# MRCS-SMC-08-Arduino-Relay.net
KiCad netlist of a schematic drawn in EAGLE
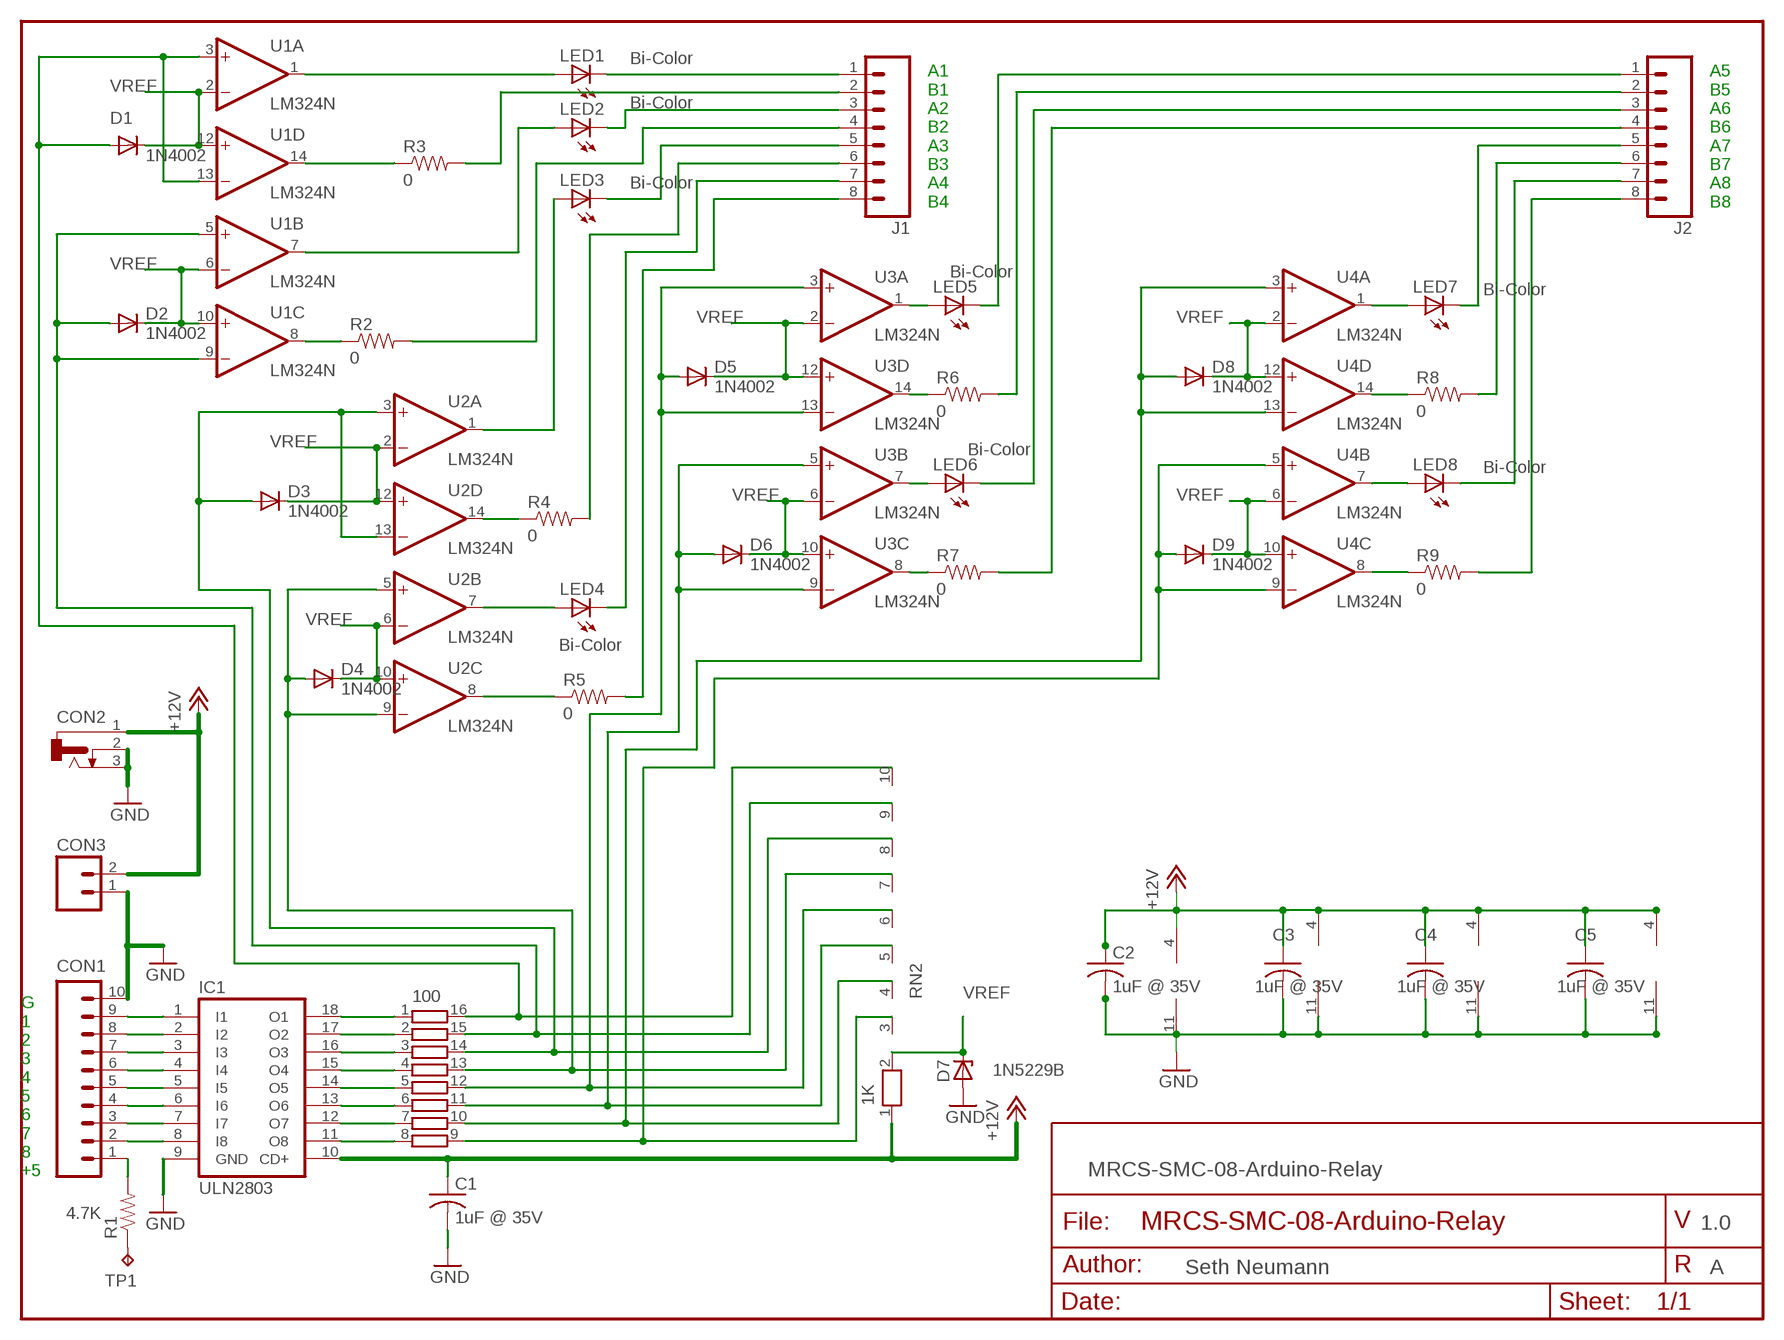
[diagram p0: schematic, sheet 1]

(export (version "E")
  (design (tool "Eeschema 10.0.6"))
  (components
    (comp (ref "C1")
      (value "1uF @ 35V")
      (footprint "eagle-import:C-PTH-0.100")
      (libsource (lib "eagle-import") (part "CAPPTH2"))
    )
    (comp (ref "C2")
      (value "1uF @ 35V")
      (footprint "eagle-import:C-PTH-0.100")
      (libsource (lib "eagle-import") (part "CAPPTH2"))
    )
    (comp (ref "C3")
      (value "1uF @ 35V")
      (footprint "eagle-import:C-PTH-0.100")
      (libsource (lib "eagle-import") (part "CAPPTH2"))
    )
    (comp (ref "C4")
      (value "1uF @ 35V")
      (footprint "eagle-import:C-PTH-0.100")
      (libsource (lib "eagle-import") (part "CAPPTH2"))
    )
    (comp (ref "C5")
      (value "1uF @ 35V")
      (footprint "eagle-import:C-PTH-0.100")
      (libsource (lib "eagle-import") (part "CAPPTH2"))
    )
    (comp (ref "CON1")
      (value "CONNECTOR-M10LOCK")
      (footprint "eagle-import:1X10_LOCK")
      (libsource (lib "eagle-import") (part "CONNECTOR-M10LOCK"))
    )
    (comp (ref "CON2")
      (value "CONNECTOR-DC-POWER-S")
      (footprint "eagle-import:DCJ0202-SMALL")
      (libsource (lib "eagle-import") (part "CONNECTOR-DC-POWER-S"))
    )
    (comp (ref "CON3")
      (value "CONNECTOR-M023.5MM-LOCK")
      (footprint "eagle-import:SCREWTERMINAL-3.5MM-2_LOCK")
      (libsource (lib "eagle-import") (part "CONNECTOR-M023.5MM-LOCK"))
    )
    (comp (ref "D1")
      (value "1N4002")
      (footprint "eagle-import:DIODE-1N4001")
      (libsource (lib "eagle-import") (part "DIODEPTH"))
    )
    (comp (ref "D2")
      (value "1N4002")
      (footprint "eagle-import:DIODE-1N4001")
      (libsource (lib "eagle-import") (part "DIODEPTH"))
    )
    (comp (ref "D3")
      (value "1N4002")
      (footprint "eagle-import:DIODE-1N4001")
      (libsource (lib "eagle-import") (part "DIODEPTH"))
    )
    (comp (ref "D4")
      (value "1N4002")
      (footprint "eagle-import:DIODE-1N4001")
      (libsource (lib "eagle-import") (part "DIODEPTH"))
    )
    (comp (ref "D5")
      (value "1N4002")
      (footprint "eagle-import:DIODE-1N4001")
      (libsource (lib "eagle-import") (part "DIODEPTH"))
    )
    (comp (ref "D6")
      (value "1N4002")
      (footprint "eagle-import:DIODE-1N4001")
      (libsource (lib "eagle-import") (part "DIODEPTH"))
    )
    (comp (ref "D7")
      (value "1N5229B")
      (footprint "eagle-import:ZDIO-5")
      (libsource (lib "eagle-import") (part "ZENER-DIODEZD-5"))
    )
    (comp (ref "D8")
      (value "1N4002")
      (footprint "eagle-import:DIODE-1N4001")
      (libsource (lib "eagle-import") (part "DIODEPTH"))
    )
    (comp (ref "D9")
      (value "1N4002")
      (footprint "eagle-import:DIODE-1N4001")
      (libsource (lib "eagle-import") (part "DIODEPTH"))
    )
    (comp (ref "IC1")
      (value "ULN2803")
      (footprint "eagle-import:DIL18")
      (libsource (lib "eagle-import") (part "ULN2803A"))
    )
    (comp (ref "J1")
      (value "CONNECTOR-M08LOCK")
      (footprint "eagle-import:1X08_LOCK")
      (libsource (lib "eagle-import") (part "CONNECTOR-M08LOCK"))
    )
    (comp (ref "J2")
      (value "CONNECTOR-M08LOCK")
      (footprint "eagle-import:1X08_LOCK")
      (libsource (lib "eagle-import") (part "CONNECTOR-M08LOCK"))
    )
    (comp (ref "LED1")
      (value "Bi-Color")
      (footprint "eagle-import:LED3MM")
      (libsource (lib "eagle-import") (part "LEDLED3MM"))
    )
    (comp (ref "LED2")
      (value "Bi-Color")
      (footprint "eagle-import:LED3MM")
      (libsource (lib "eagle-import") (part "LEDLED3MM"))
    )
    (comp (ref "LED3")
      (value "Bi-Color")
      (footprint "eagle-import:LED3MM")
      (libsource (lib "eagle-import") (part "LEDLED3MM"))
    )
    (comp (ref "LED4")
      (value "Bi-Color")
      (footprint "eagle-import:LED3MM")
      (libsource (lib "eagle-import") (part "LEDLED3MM"))
    )
    (comp (ref "LED5")
      (value "Bi-Color")
      (footprint "eagle-import:LED3MM")
      (libsource (lib "eagle-import") (part "LEDLED3MM"))
    )
    (comp (ref "LED6")
      (value "Bi-Color")
      (footprint "eagle-import:LED3MM")
      (libsource (lib "eagle-import") (part "LEDLED3MM"))
    )
    (comp (ref "LED7")
      (value "Bi-Color")
      (footprint "eagle-import:LED3MM")
      (libsource (lib "eagle-import") (part "LEDLED3MM"))
    )
    (comp (ref "LED8")
      (value "Bi-Color")
      (footprint "eagle-import:LED3MM")
      (libsource (lib "eagle-import") (part "LEDLED3MM"))
    )
    (comp (ref "R1")
      (value "4.7K")
      (footprint "eagle-import:AXIAL-0.4-RES")
      (libsource (lib "eagle-import") (part "RPTH04"))
    )
    (comp (ref "R2")
      (value "0")
      (footprint "eagle-import:CUT-R")
      (libsource (lib "eagle-import") (part "RPTH-R0"))
    )
    (comp (ref "R3")
      (value "0")
      (footprint "eagle-import:CUT-R")
      (libsource (lib "eagle-import") (part "RPTH-R0"))
    )
    (comp (ref "R4")
      (value "0")
      (footprint "eagle-import:CUT-R")
      (libsource (lib "eagle-import") (part "RPTH-R0"))
    )
    (comp (ref "R5")
      (value "0")
      (footprint "eagle-import:CUT-R")
      (libsource (lib "eagle-import") (part "RPTH-R0"))
    )
    (comp (ref "R6")
      (value "0")
      (footprint "eagle-import:CUT-R")
      (libsource (lib "eagle-import") (part "RPTH-R0"))
    )
    (comp (ref "R7")
      (value "0")
      (footprint "eagle-import:CUT-R")
      (libsource (lib "eagle-import") (part "RPTH-R0"))
    )
    (comp (ref "R8")
      (value "0")
      (footprint "eagle-import:CUT-R")
      (libsource (lib "eagle-import") (part "RPTH-R0"))
    )
    (comp (ref "R9")
      (value "0")
      (footprint "eagle-import:CUT-R")
      (libsource (lib "eagle-import") (part "RPTH-R0"))
    )
    (comp (ref "RN1")
      (value "100")
      (footprint "eagle-import:DIL16")
      (libsource (lib "eagle-import") (part "8R-N"))
    )
    (comp (ref "RN2")
      (value "1K")
      (footprint "eagle-import:RN-10")
      (libsource (lib "eagle-import") (part "RN09"))
    )
    (comp (ref "TP1")
      (value "TPPAD1-13")
      (footprint "eagle-import:P1-13")
      (libsource (lib "eagle-import") (part "TPPAD1-13"))
    )
    (comp (ref "U1")
      (value "LM324N")
      (footprint "eagle-import:DIL14")
      (libsource (lib "eagle-import") (part "LM324N"))
    )
    (comp (ref "U2")
      (value "LM324N")
      (footprint "eagle-import:DIL14")
      (libsource (lib "eagle-import") (part "LM324N"))
    )
    (comp (ref "U3")
      (value "LM324N")
      (footprint "eagle-import:DIL14")
      (libsource (lib "eagle-import") (part "LM324N"))
    )
    (comp (ref "U4")
      (value "LM324N")
      (footprint "eagle-import:DIL14")
      (libsource (lib "eagle-import") (part "LM324N"))
    )
  )
  (nets
    (net (code "1") (name "+12V") (class "Default")
      (node (ref "C1") (pin "1") (pinfunction "1_1") (pintype "passive"))
      (node (ref "C2") (pin "1") (pinfunction "1_1") (pintype "passive"))
      (node (ref "C3") (pin "1") (pinfunction "1_1") (pintype "passive"))
      (node (ref "C4") (pin "1") (pinfunction "1_1") (pintype "passive"))
      (node (ref "C5") (pin "1") (pinfunction "1_1") (pintype "passive"))
      (node (ref "CON2") (pin "1") (pinfunction "1_1") (pintype "passive"))
      (node (ref "CON3") (pin "2") (pinfunction "B_2") (pintype "passive"))
      (node (ref "IC1") (pin "10") (pinfunction "CD+_10") (pintype "passive"))
      (node (ref "RN2") (pin "1") (pinfunction "1_1") (pintype "passive"))
      (node (ref "U1") (pin "4") (pinfunction "V+_4") (pintype "power_in"))
      (node (ref "U2") (pin "4") (pinfunction "V+_4") (pintype "power_in"))
      (node (ref "U3") (pin "4") (pinfunction "V+_4") (pintype "power_in"))
      (node (ref "U4") (pin "4") (pinfunction "V+_4") (pintype "power_in"))
    )
    (net (code "2") (name "/VREF") (class "Default")
      (node (ref "D1") (pin "C") (pinfunction "C_C") (pintype "passive"))
      (node (ref "D2") (pin "C") (pinfunction "C_C") (pintype "passive"))
      (node (ref "D3") (pin "C") (pinfunction "C_C") (pintype "passive"))
      (node (ref "D4") (pin "C") (pinfunction "C_C") (pintype "passive"))
      (node (ref "D5") (pin "C") (pinfunction "C_C") (pintype "passive"))
      (node (ref "D6") (pin "C") (pinfunction "C_C") (pintype "passive"))
      (node (ref "D7") (pin "C") (pinfunction "C_C") (pintype "passive"))
      (node (ref "D8") (pin "C") (pinfunction "C_C") (pintype "passive"))
      (node (ref "D9") (pin "C") (pinfunction "C_C") (pintype "passive"))
      (node (ref "RN2") (pin "2") (pinfunction "2_2") (pintype "passive"))
      (node (ref "U1") (pin "10") (pinfunction "+IN_10") (pintype "input"))
      (node (ref "U1") (pin "12") (pinfunction "+IN_12") (pintype "input"))
      (node (ref "U1") (pin "2") (pinfunction "-IN_2") (pintype "input"))
      (node (ref "U1") (pin "6") (pinfunction "-IN_6") (pintype "input"))
      (node (ref "U2") (pin "10") (pinfunction "+IN_10") (pintype "input"))
      (node (ref "U2") (pin "12") (pinfunction "+IN_12") (pintype "input"))
      (node (ref "U2") (pin "2") (pinfunction "-IN_2") (pintype "input"))
      (node (ref "U2") (pin "6") (pinfunction "-IN_6") (pintype "input"))
      (node (ref "U3") (pin "10") (pinfunction "+IN_10") (pintype "input"))
      (node (ref "U3") (pin "12") (pinfunction "+IN_12") (pintype "input"))
      (node (ref "U3") (pin "2") (pinfunction "-IN_2") (pintype "input"))
      (node (ref "U3") (pin "6") (pinfunction "-IN_6") (pintype "input"))
      (node (ref "U4") (pin "10") (pinfunction "+IN_10") (pintype "input"))
      (node (ref "U4") (pin "12") (pinfunction "+IN_12") (pintype "input"))
      (node (ref "U4") (pin "2") (pinfunction "-IN_2") (pintype "input"))
      (node (ref "U4") (pin "6") (pinfunction "-IN_6") (pintype "input"))
    )
    (net (code "3") (name "GND") (class "Default")
      (node (ref "C1") (pin "2") (pinfunction "2_2") (pintype "passive"))
      (node (ref "C2") (pin "2") (pinfunction "2_2") (pintype "passive"))
      (node (ref "C3") (pin "2") (pinfunction "2_2") (pintype "passive"))
      (node (ref "C4") (pin "2") (pinfunction "2_2") (pintype "passive"))
      (node (ref "C5") (pin "2") (pinfunction "2_2") (pintype "passive"))
      (node (ref "CON1") (pin "10") (pinfunction "10_10") (pintype "passive"))
      (node (ref "CON2") (pin "2") (pinfunction "2_2") (pintype "passive"))
      (node (ref "CON2") (pin "3") (pinfunction "3_3") (pintype "passive"))
      (node (ref "CON3") (pin "1") (pinfunction "A_1") (pintype "passive"))
      (node (ref "D7") (pin "A") (pinfunction "A_A") (pintype "passive"))
      (node (ref "IC1") (pin "9") (pinfunction "GND_9") (pintype "power_in"))
      (node (ref "U1") (pin "11") (pinfunction "V-_11") (pintype "power_in"))
      (node (ref "U2") (pin "11") (pinfunction "V-_11") (pintype "power_in"))
      (node (ref "U3") (pin "11") (pinfunction "V-_11") (pintype "power_in"))
      (node (ref "U4") (pin "11") (pinfunction "V-_11") (pintype "power_in"))
    )
    (net (code "4") (name "Net-(IC1-I1)") (class "Default")
      (node (ref "CON1") (pin "9") (pinfunction "9_9") (pintype "passive"))
      (node (ref "IC1") (pin "1") (pinfunction "I1_1") (pintype "input"))
    )
    (net (code "5") (name "Net-(IC1-I2)") (class "Default")
      (node (ref "CON1") (pin "8") (pinfunction "8_8") (pintype "passive"))
      (node (ref "IC1") (pin "2") (pinfunction "I2_2") (pintype "input"))
    )
    (net (code "6") (name "Net-(IC1-I3)") (class "Default")
      (node (ref "CON1") (pin "7") (pinfunction "7_7") (pintype "passive"))
      (node (ref "IC1") (pin "3") (pinfunction "I3_3") (pintype "input"))
    )
    (net (code "7") (name "Net-(IC1-I4)") (class "Default")
      (node (ref "CON1") (pin "6") (pinfunction "6_6") (pintype "passive"))
      (node (ref "IC1") (pin "4") (pinfunction "I4_4") (pintype "input"))
    )
    (net (code "8") (name "Net-(IC1-I5)") (class "Default")
      (node (ref "CON1") (pin "5") (pinfunction "5_5") (pintype "passive"))
      (node (ref "IC1") (pin "5") (pinfunction "I5_5") (pintype "input"))
    )
    (net (code "9") (name "Net-(IC1-I6)") (class "Default")
      (node (ref "CON1") (pin "4") (pinfunction "4_4") (pintype "passive"))
      (node (ref "IC1") (pin "6") (pinfunction "I6_6") (pintype "input"))
    )
    (net (code "10") (name "Net-(IC1-I7)") (class "Default")
      (node (ref "CON1") (pin "3") (pinfunction "3_3") (pintype "passive"))
      (node (ref "IC1") (pin "7") (pinfunction "I7_7") (pintype "input"))
    )
    (net (code "11") (name "Net-(IC1-I8)") (class "Default")
      (node (ref "CON1") (pin "2") (pinfunction "2_2") (pintype "passive"))
      (node (ref "IC1") (pin "8") (pinfunction "I8_8") (pintype "input"))
    )
    (net (code "12") (name "Net-(IC1-O1)") (class "Default")
      (node (ref "IC1") (pin "18") (pinfunction "O1_18") (pintype "open_collector"))
      (node (ref "RN1") (pin "1") (pinfunction "1_1") (pintype "passive"))
    )
    (net (code "13") (name "Net-(IC1-O2)") (class "Default")
      (node (ref "IC1") (pin "17") (pinfunction "O2_17") (pintype "open_collector"))
      (node (ref "RN1") (pin "2") (pinfunction "1_2") (pintype "passive"))
    )
    (net (code "14") (name "Net-(IC1-O3)") (class "Default")
      (node (ref "IC1") (pin "16") (pinfunction "O3_16") (pintype "open_collector"))
      (node (ref "RN1") (pin "3") (pinfunction "1_3") (pintype "passive"))
    )
    (net (code "15") (name "Net-(IC1-O4)") (class "Default")
      (node (ref "IC1") (pin "15") (pinfunction "O4_15") (pintype "open_collector"))
      (node (ref "RN1") (pin "4") (pinfunction "1_4") (pintype "passive"))
    )
    (net (code "16") (name "Net-(IC1-O5)") (class "Default")
      (node (ref "IC1") (pin "14") (pinfunction "O5_14") (pintype "open_collector"))
      (node (ref "RN1") (pin "5") (pinfunction "1_5") (pintype "passive"))
    )
    (net (code "17") (name "Net-(IC1-O6)") (class "Default")
      (node (ref "IC1") (pin "13") (pinfunction "O6_13") (pintype "open_collector"))
      (node (ref "RN1") (pin "6") (pinfunction "1_6") (pintype "passive"))
    )
    (net (code "18") (name "Net-(IC1-O7)") (class "Default")
      (node (ref "IC1") (pin "12") (pinfunction "O7_12") (pintype "open_collector"))
      (node (ref "RN1") (pin "7") (pinfunction "1_7") (pintype "passive"))
    )
    (net (code "19") (name "Net-(IC1-O8)") (class "Default")
      (node (ref "IC1") (pin "11") (pinfunction "O8_11") (pintype "open_collector"))
      (node (ref "RN1") (pin "8") (pinfunction "1_8") (pintype "passive"))
    )
    (net (code "20") (name "Net-(LED1-C)") (class "Default")
      (node (ref "J1") (pin "1") (pinfunction "1_1") (pintype "passive"))
      (node (ref "LED1") (pin "K") (pinfunction "C_K") (pintype "passive"))
    )
    (net (code "21") (name "Net-(LED2-C)") (class "Default")
      (node (ref "J1") (pin "3") (pinfunction "3_3") (pintype "passive"))
      (node (ref "LED2") (pin "K") (pinfunction "C_K") (pintype "passive"))
    )
    (net (code "22") (name "Net-(LED3-C)") (class "Default")
      (node (ref "J1") (pin "5") (pinfunction "5_5") (pintype "passive"))
      (node (ref "LED3") (pin "K") (pinfunction "C_K") (pintype "passive"))
    )
    (net (code "23") (name "Net-(LED4-C)") (class "Default")
      (node (ref "J1") (pin "7") (pinfunction "7_7") (pintype "passive"))
      (node (ref "LED4") (pin "K") (pinfunction "C_K") (pintype "passive"))
    )
    (net (code "24") (name "Net-(LED5-C)") (class "Default")
      (node (ref "J2") (pin "1") (pinfunction "1_1") (pintype "passive"))
      (node (ref "LED5") (pin "K") (pinfunction "C_K") (pintype "passive"))
    )
    (net (code "25") (name "Net-(LED6-C)") (class "Default")
      (node (ref "J2") (pin "3") (pinfunction "3_3") (pintype "passive"))
      (node (ref "LED6") (pin "K") (pinfunction "C_K") (pintype "passive"))
    )
    (net (code "26") (name "Net-(LED7-C)") (class "Default")
      (node (ref "J2") (pin "5") (pinfunction "5_5") (pintype "passive"))
      (node (ref "LED7") (pin "K") (pinfunction "C_K") (pintype "passive"))
    )
    (net (code "27") (name "Net-(LED8-C)") (class "Default")
      (node (ref "J2") (pin "7") (pinfunction "7_7") (pintype "passive"))
      (node (ref "LED8") (pin "K") (pinfunction "C_K") (pintype "passive"))
    )
    (net (code "28") (name "Net-(R1-1)") (class "Default")
      (node (ref "R1") (pin "P$1") (pinfunction "1_P$1") (pintype "passive"))
      (node (ref "TP1") (pin "TP") (pinfunction "TP_TP") (pintype "input"))
    )
    (net (code "29") (name "Net-(R1-2)") (class "Default")
      (node (ref "CON1") (pin "1") (pinfunction "1_1") (pintype "passive"))
      (node (ref "R1") (pin "P$2") (pinfunction "2_P$2") (pintype "passive"))
    )
    (net (code "30") (name "Net-(R2-1)") (class "Default")
      (node (ref "R2") (pin "P2") (pinfunction "1_P2") (pintype "passive"))
      (node (ref "U1") (pin "8") (pinfunction "OUT_8") (pintype "output"))
    )
    (net (code "31") (name "Net-(R2-2)") (class "Default")
      (node (ref "J1") (pin "4") (pinfunction "4_4") (pintype "passive"))
      (node (ref "R2") (pin "P1") (pinfunction "2_P1") (pintype "passive"))
    )
    (net (code "32") (name "Net-(R3-1)") (class "Default")
      (node (ref "R3") (pin "P2") (pinfunction "1_P2") (pintype "passive"))
      (node (ref "U1") (pin "14") (pinfunction "OUT_14") (pintype "output"))
    )
    (net (code "33") (name "Net-(R3-2)") (class "Default")
      (node (ref "J1") (pin "2") (pinfunction "2_2") (pintype "passive"))
      (node (ref "R3") (pin "P1") (pinfunction "2_P1") (pintype "passive"))
    )
    (net (code "34") (name "Net-(R4-1)") (class "Default")
      (node (ref "R4") (pin "P2") (pinfunction "1_P2") (pintype "passive"))
      (node (ref "U2") (pin "14") (pinfunction "OUT_14") (pintype "output"))
    )
    (net (code "35") (name "Net-(R4-2)") (class "Default")
      (node (ref "J1") (pin "6") (pinfunction "6_6") (pintype "passive"))
      (node (ref "R4") (pin "P1") (pinfunction "2_P1") (pintype "passive"))
    )
    (net (code "36") (name "Net-(R5-1)") (class "Default")
      (node (ref "R5") (pin "P2") (pinfunction "1_P2") (pintype "passive"))
      (node (ref "U2") (pin "8") (pinfunction "OUT_8") (pintype "output"))
    )
    (net (code "37") (name "Net-(R5-2)") (class "Default")
      (node (ref "J1") (pin "8") (pinfunction "8_8") (pintype "passive"))
      (node (ref "R5") (pin "P1") (pinfunction "2_P1") (pintype "passive"))
    )
    (net (code "38") (name "Net-(R6-1)") (class "Default")
      (node (ref "R6") (pin "P2") (pinfunction "1_P2") (pintype "passive"))
      (node (ref "U3") (pin "14") (pinfunction "OUT_14") (pintype "output"))
    )
    (net (code "39") (name "Net-(R6-2)") (class "Default")
      (node (ref "J2") (pin "2") (pinfunction "2_2") (pintype "passive"))
      (node (ref "R6") (pin "P1") (pinfunction "2_P1") (pintype "passive"))
    )
    (net (code "40") (name "Net-(R7-1)") (class "Default")
      (node (ref "R7") (pin "P2") (pinfunction "1_P2") (pintype "passive"))
      (node (ref "U3") (pin "8") (pinfunction "OUT_8") (pintype "output"))
    )
    (net (code "41") (name "Net-(R7-2)") (class "Default")
      (node (ref "J2") (pin "4") (pinfunction "4_4") (pintype "passive"))
      (node (ref "R7") (pin "P1") (pinfunction "2_P1") (pintype "passive"))
    )
    (net (code "42") (name "Net-(R8-1)") (class "Default")
      (node (ref "R8") (pin "P2") (pinfunction "1_P2") (pintype "passive"))
      (node (ref "U4") (pin "14") (pinfunction "OUT_14") (pintype "output"))
    )
    (net (code "43") (name "Net-(R8-2)") (class "Default")
      (node (ref "J2") (pin "6") (pinfunction "6_6") (pintype "passive"))
      (node (ref "R8") (pin "P1") (pinfunction "2_P1") (pintype "passive"))
    )
    (net (code "44") (name "Net-(R9-1)") (class "Default")
      (node (ref "R9") (pin "P2") (pinfunction "1_P2") (pintype "passive"))
      (node (ref "U4") (pin "8") (pinfunction "OUT_8") (pintype "output"))
    )
    (net (code "45") (name "Net-(R9-2)") (class "Default")
      (node (ref "J2") (pin "8") (pinfunction "8_8") (pintype "passive"))
      (node (ref "R9") (pin "P1") (pinfunction "2_P1") (pintype "passive"))
    )
    (net (code "46") (name "Net-(RN1A-2)") (class "Default")
      (node (ref "D1") (pin "A") (pinfunction "A_A") (pintype "passive"))
      (node (ref "RN1") (pin "16") (pinfunction "2_16") (pintype "passive"))
      (node (ref "RN2") (pin "10") (pinfunction "10_10") (pintype "passive"))
      (node (ref "U1") (pin "13") (pinfunction "-IN_13") (pintype "input"))
      (node (ref "U1") (pin "3") (pinfunction "+IN_3") (pintype "input"))
    )
    (net (code "47") (name "Net-(RN1B-2)") (class "Default")
      (node (ref "D2") (pin "A") (pinfunction "A_A") (pintype "passive"))
      (node (ref "RN1") (pin "15") (pinfunction "2_15") (pintype "passive"))
      (node (ref "RN2") (pin "9") (pinfunction "9_9") (pintype "passive"))
      (node (ref "U1") (pin "5") (pinfunction "+IN_5") (pintype "input"))
      (node (ref "U1") (pin "9") (pinfunction "-IN_9") (pintype "input"))
    )
    (net (code "48") (name "Net-(RN1C-2)") (class "Default")
      (node (ref "D3") (pin "A") (pinfunction "A_A") (pintype "passive"))
      (node (ref "RN1") (pin "14") (pinfunction "2_14") (pintype "passive"))
      (node (ref "RN2") (pin "8") (pinfunction "8_8") (pintype "passive"))
      (node (ref "U2") (pin "13") (pinfunction "-IN_13") (pintype "input"))
      (node (ref "U2") (pin "3") (pinfunction "+IN_3") (pintype "input"))
    )
    (net (code "49") (name "Net-(RN1D-2)") (class "Default")
      (node (ref "D4") (pin "A") (pinfunction "A_A") (pintype "passive"))
      (node (ref "RN1") (pin "13") (pinfunction "2_13") (pintype "passive"))
      (node (ref "RN2") (pin "7") (pinfunction "7_7") (pintype "passive"))
      (node (ref "U2") (pin "5") (pinfunction "+IN_5") (pintype "input"))
      (node (ref "U2") (pin "9") (pinfunction "-IN_9") (pintype "input"))
    )
    (net (code "50") (name "Net-(RN1E-2)") (class "Default")
      (node (ref "D5") (pin "A") (pinfunction "A_A") (pintype "passive"))
      (node (ref "RN1") (pin "12") (pinfunction "2_12") (pintype "passive"))
      (node (ref "RN2") (pin "6") (pinfunction "6_6") (pintype "passive"))
      (node (ref "U3") (pin "13") (pinfunction "-IN_13") (pintype "input"))
      (node (ref "U3") (pin "3") (pinfunction "+IN_3") (pintype "input"))
    )
    (net (code "51") (name "Net-(RN1F-2)") (class "Default")
      (node (ref "D6") (pin "A") (pinfunction "A_A") (pintype "passive"))
      (node (ref "RN1") (pin "11") (pinfunction "2_11") (pintype "passive"))
      (node (ref "RN2") (pin "5") (pinfunction "5_5") (pintype "passive"))
      (node (ref "U3") (pin "5") (pinfunction "+IN_5") (pintype "input"))
      (node (ref "U3") (pin "9") (pinfunction "-IN_9") (pintype "input"))
    )
    (net (code "52") (name "Net-(RN1G-2)") (class "Default")
      (node (ref "D8") (pin "A") (pinfunction "A_A") (pintype "passive"))
      (node (ref "RN1") (pin "10") (pinfunction "2_10") (pintype "passive"))
      (node (ref "RN2") (pin "4") (pinfunction "4_4") (pintype "passive"))
      (node (ref "U4") (pin "13") (pinfunction "-IN_13") (pintype "input"))
      (node (ref "U4") (pin "3") (pinfunction "+IN_3") (pintype "input"))
    )
    (net (code "53") (name "Net-(RN1H-2)") (class "Default")
      (node (ref "D9") (pin "A") (pinfunction "A_A") (pintype "passive"))
      (node (ref "RN1") (pin "9") (pinfunction "2_9") (pintype "passive"))
      (node (ref "RN2") (pin "3") (pinfunction "3_3") (pintype "passive"))
      (node (ref "U4") (pin "5") (pinfunction "+IN_5") (pintype "input"))
      (node (ref "U4") (pin "9") (pinfunction "-IN_9") (pintype "input"))
    )
    (net (code "54") (name "Net-(U1A-OUT)") (class "Default")
      (node (ref "LED1") (pin "A") (pinfunction "A_A") (pintype "passive"))
      (node (ref "U1") (pin "1") (pinfunction "OUT_1") (pintype "output"))
    )
    (net (code "55") (name "Net-(U1B-OUT)") (class "Default")
      (node (ref "LED2") (pin "A") (pinfunction "A_A") (pintype "passive"))
      (node (ref "U1") (pin "7") (pinfunction "OUT_7") (pintype "output"))
    )
    (net (code "56") (name "Net-(U2A-OUT)") (class "Default")
      (node (ref "LED3") (pin "A") (pinfunction "A_A") (pintype "passive"))
      (node (ref "U2") (pin "1") (pinfunction "OUT_1") (pintype "output"))
    )
    (net (code "57") (name "Net-(U2B-OUT)") (class "Default")
      (node (ref "LED4") (pin "A") (pinfunction "A_A") (pintype "passive"))
      (node (ref "U2") (pin "7") (pinfunction "OUT_7") (pintype "output"))
    )
    (net (code "58") (name "Net-(U3A-OUT)") (class "Default")
      (node (ref "LED5") (pin "A") (pinfunction "A_A") (pintype "passive"))
      (node (ref "U3") (pin "1") (pinfunction "OUT_1") (pintype "output"))
    )
    (net (code "59") (name "Net-(U3B-OUT)") (class "Default")
      (node (ref "LED6") (pin "A") (pinfunction "A_A") (pintype "passive"))
      (node (ref "U3") (pin "7") (pinfunction "OUT_7") (pintype "output"))
    )
    (net (code "60") (name "Net-(U4A-OUT)") (class "Default")
      (node (ref "LED7") (pin "A") (pinfunction "A_A") (pintype "passive"))
      (node (ref "U4") (pin "1") (pinfunction "OUT_1") (pintype "output"))
    )
    (net (code "61") (name "Net-(U4B-OUT)") (class "Default")
      (node (ref "LED8") (pin "A") (pinfunction "A_A") (pintype "passive"))
      (node (ref "U4") (pin "7") (pinfunction "OUT_7") (pintype "output"))
    )
  )
)
